# HelpfulHallway.net
KiCad netlist of a schematic drawn in EAGLE
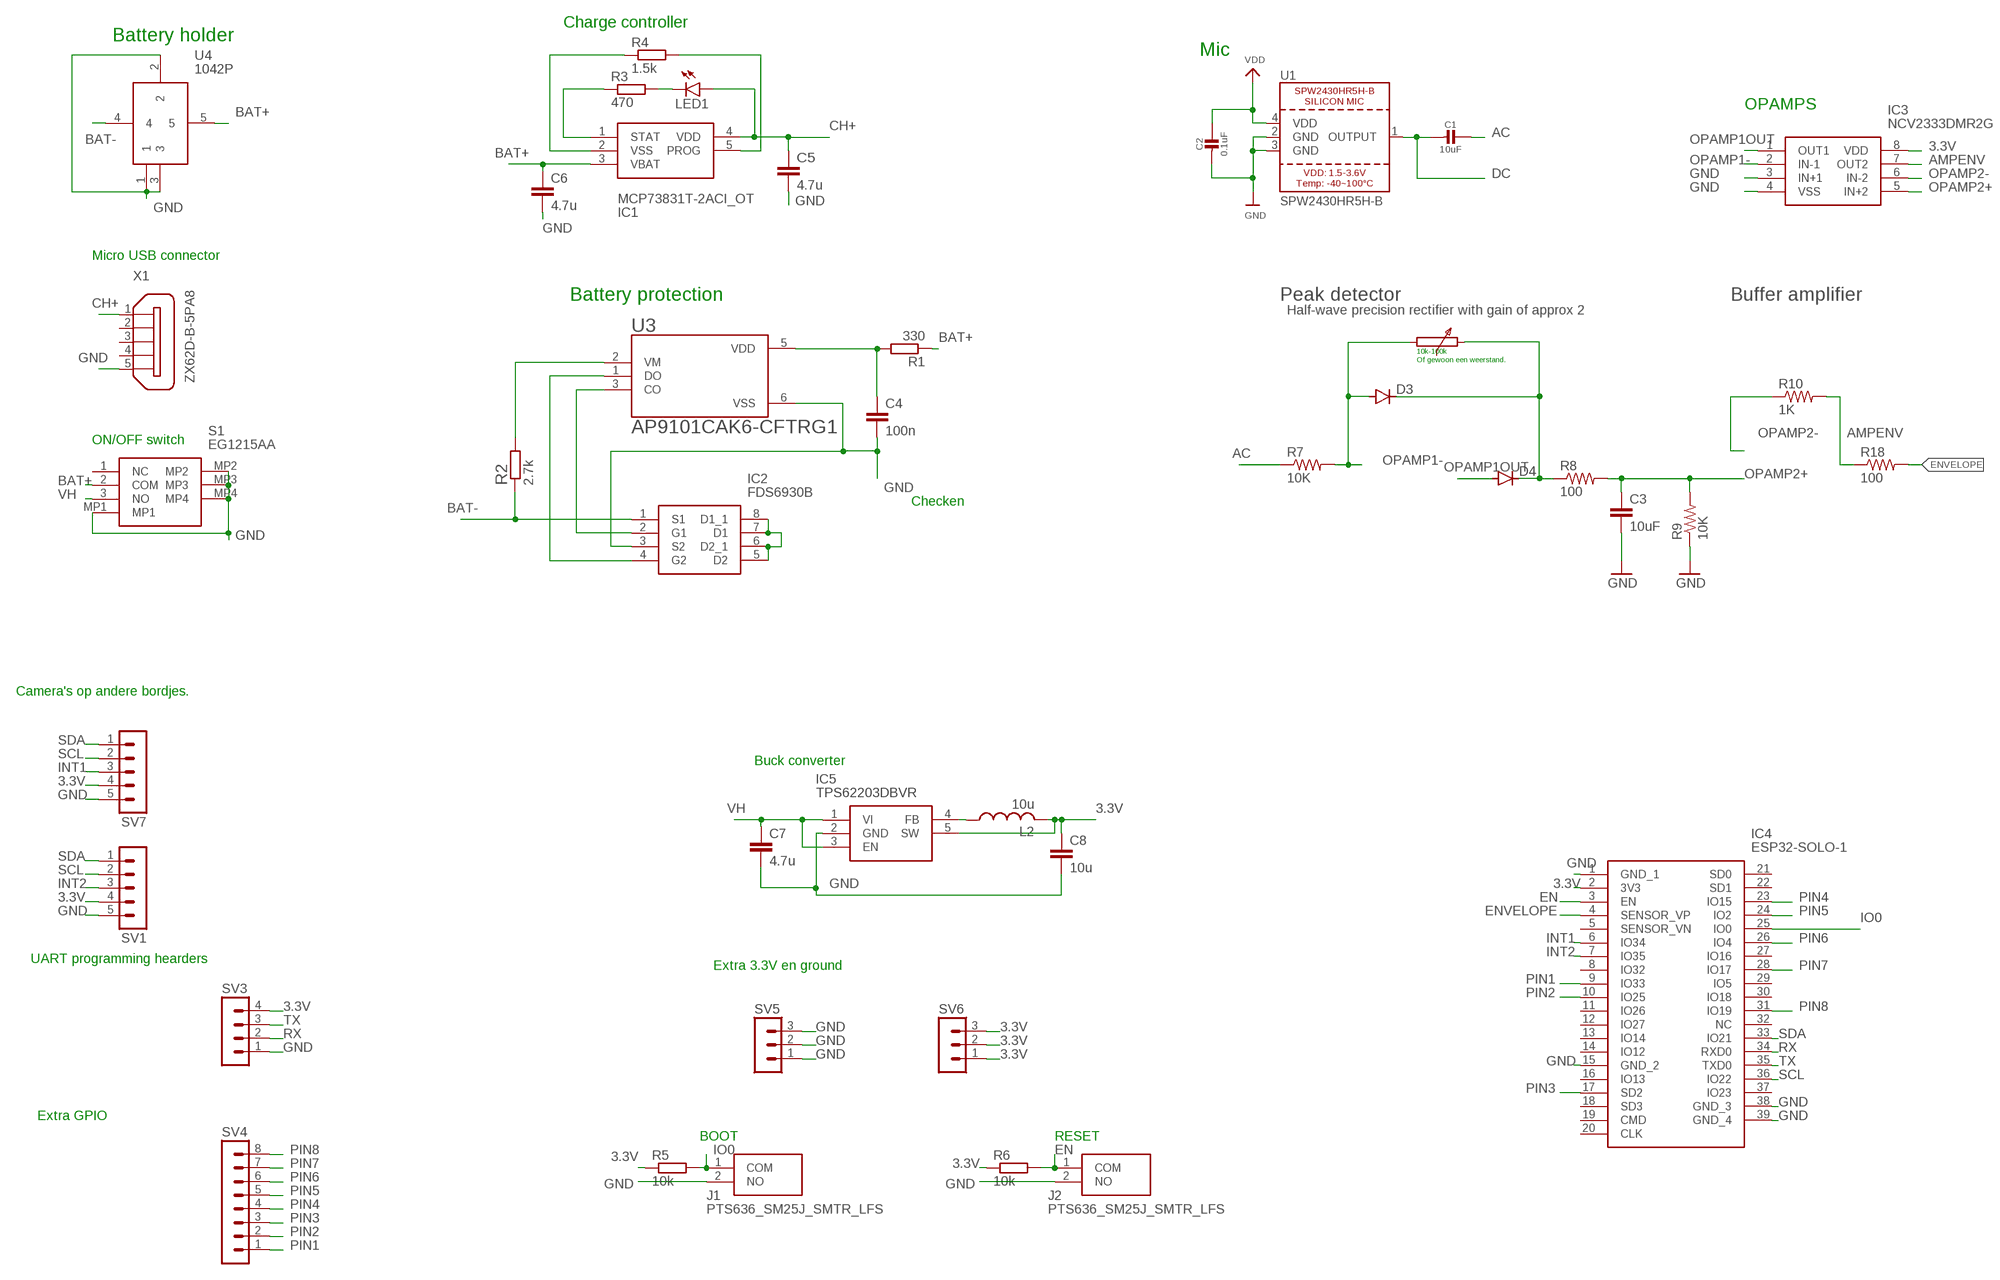
[diagram p0: schematic, sheet 1]

(export (version "E")
  (design (tool "Eeschema 10.0.6"))
  (components
    (comp (ref "C1")
      (value "10uF")
      (footprint "eagle-import:0805-NO")
      (libsource (lib "eagle-import") (part "CAP_CERAMIC0805-NOOUTLINE"))
    )
    (comp (ref "C2")
      (value "0.1uF")
      (footprint "eagle-import:0805-NO")
      (libsource (lib "eagle-import") (part "CAP_CERAMIC0805-NOOUTLINE"))
    )
    (comp (ref "C3")
      (value "10uF")
      (footprint "eagle-import:1206")
      (libsource (lib "eagle-import") (part "10UF-6.3V-20%(1206)"))
    )
    (comp (ref "C4")
      (value "100n")
      (footprint "eagle-import:C1206")
      (libsource (lib "eagle-import") (part "C-EUC1206"))
    )
    (comp (ref "C5")
      (value "4.7u")
      (footprint "eagle-import:C1206")
      (libsource (lib "eagle-import") (part "C-EUC1206"))
    )
    (comp (ref "C6")
      (value "4.7u")
      (footprint "eagle-import:C1206")
      (libsource (lib "eagle-import") (part "C-EUC1206"))
    )
    (comp (ref "C7")
      (value "4.7u")
      (footprint "eagle-import:C1206")
      (libsource (lib "eagle-import") (part "C-EUC1206"))
    )
    (comp (ref "C8")
      (value "10u")
      (footprint "eagle-import:C1206")
      (libsource (lib "eagle-import") (part "C-EUC1206"))
    )
    (comp (ref "D3")
      (value "DIODE-SOD123")
      (footprint "eagle-import:SOD123")
      (libsource (lib "eagle-import") (part "DIODE-SOD123"))
    )
    (comp (ref "D4")
      (value "DIODE-SOD123")
      (footprint "eagle-import:SOD123")
      (libsource (lib "eagle-import") (part "DIODE-SOD123"))
    )
    (comp (ref "IC1")
      (value "MCP73831T-2ACI_OT")
      (footprint "eagle-import:SOT95P270X145-5N")
      (fields
        (field (name "MANUFACTURER_PART_NUMBER") "MCP73831T-2ACI/OT")
        (field (name "MOUSER_PART_NUMBER") "579-MCP73831T-2ACIOT")
      )
      (libsource (lib "eagle-import") (part "MCP73831T-2ACI_OT"))
    )
    (comp (ref "IC2")
      (value "FDS6930B")
      (footprint "eagle-import:SOIC127P600X175-8N")
      (fields (field (name "MOUSER_PART_NUMBER") "512-FDS6930B"))
      (libsource (lib "eagle-import") (part "FDS6930B"))
    )
    (comp (ref "IC3")
      (value "NCV2333DMR2G")
      (footprint "eagle-import:SOP65P490X110-8N")
      (fields (field (name "MOUSER_PART_NUMBER") "863-NCV2333DMR2G"))
      (libsource (lib "eagle-import") (part "NCV2333DMR2G"))
    )
    (comp (ref "IC4")
      (value "ESP32-SOLO-1")
      (footprint "eagle-import:ESP32SOLO1")
      (fields (field (name "MOUSER_PART_NUMBER") "356-ESP32-SOLO-1"))
      (libsource (lib "eagle-import") (part "ESP32-SOLO-1"))
    )
    (comp (ref "IC5")
      (value "TPS62203DBVR")
      (footprint "eagle-import:SOT95P280X145-5N")
      (fields (field (name "MOUSER_PART_NUMBER") "595-TPS62203DBVR"))
      (libsource (lib "eagle-import") (part "TPS62203DBVR"))
    )
    (comp (ref "J1")
      (value "PTS636_SM25J_SMTR_LFS")
      (footprint "eagle-import:PTS636SM25JSMTRLFS")
      (fields
        (field (name "MANUFACTURER_PART_NUMBER") "PTS636 SM25J SMTR LFS")
        (field (name "MOUSER_PART_NUMBER") "611-PTS636SM25JSMTRL")
      )
      (libsource (lib "eagle-import") (part "PTS636_SM25J_SMTR_LFS"))
    )
    (comp (ref "J2")
      (value "PTS636_SM25J_SMTR_LFS")
      (footprint "eagle-import:PTS636SM25JSMTRLFS")
      (fields
        (field (name "MANUFACTURER_PART_NUMBER") "PTS636 SM25J SMTR LFS")
        (field (name "MOUSER_PART_NUMBER") "611-PTS636SM25JSMTRL")
      )
      (libsource (lib "eagle-import") (part "PTS636_SM25J_SMTR_LFS"))
    )
    (comp (ref "L2")
      (value "10u")
      (footprint "eagle-import:L4532P")
      (libsource (lib "eagle-import") (part "L-USL4532P"))
    )
    (comp (ref "LED1")
      (value "LEDSMT1206")
      (footprint "eagle-import:1206")
      (libsource (lib "eagle-import") (part "LEDSMT1206"))
    )
    (comp (ref "R1")
      (value "330")
      (footprint "eagle-import:R1206")
      (libsource (lib "eagle-import") (part "resistor_348_R-EU_R1206"))
    )
    (comp (ref "R2")
      (value "2.7k")
      (footprint "eagle-import:R1206")
      (libsource (lib "eagle-import") (part "resistor_348_R-EU_R1206"))
    )
    (comp (ref "R3")
      (value "470")
      (footprint "eagle-import:R1206")
      (libsource (lib "eagle-import") (part "resistor_348_R-EU_R1206"))
    )
    (comp (ref "R4")
      (value "1.5k")
      (footprint "eagle-import:R1206")
      (libsource (lib "eagle-import") (part "R-EU_R1206"))
    )
    (comp (ref "R5")
      (value "10k")
      (footprint "eagle-import:M1206")
      (libsource (lib "eagle-import") (part "R-EU_M1206"))
    )
    (comp (ref "R6")
      (value "10k")
      (footprint "eagle-import:M1206")
      (libsource (lib "eagle-import") (part "R-EU_M1206"))
    )
    (comp (ref "R7")
      (value "10K")
      (footprint "eagle-import:0603-RES")
      (libsource (lib "eagle-import") (part "10KOHM1/10W1%(0603)0603"))
    )
    (comp (ref "R8")
      (value "100")
      (footprint "eagle-import:0603-RES")
      (libsource (lib "eagle-import") (part "100OHM1/10W1%(0603)"))
    )
    (comp (ref "R9")
      (value "10K")
      (footprint "eagle-import:0603-RES")
      (libsource (lib "eagle-import") (part "10KOHM1/10W1%(0603)0603"))
    )
    (comp (ref "R10")
      (value "1K")
      (footprint "eagle-import:0603-RES")
      (libsource (lib "eagle-import") (part "1KOHM1/10W1%(0603)"))
    )
    (comp (ref "R18")
      (value "100")
      (footprint "eagle-import:0603-RES")
      (libsource (lib "eagle-import") (part "100OHM1/10W1%(0603)"))
    )
    (comp (ref "S1")
      (value "EG1215AA")
      (footprint "eagle-import:EG1215AA")
      (fields (field (name "MOUSER_PART_NUMBER") "612-EG1215AA"))
      (libsource (lib "eagle-import") (part "EG1215AA"))
    )
    (comp (ref "SV1")
      (value "MA05-1")
      (footprint "eagle-import:MA05-1")
      (libsource (lib "eagle-import") (part "MA05-1"))
    )
    (comp (ref "SV3")
      (value "MA04-1")
      (footprint "eagle-import:MA04-1")
      (libsource (lib "eagle-import") (part "MA04-1"))
    )
    (comp (ref "SV4")
      (value "MA08-1")
      (footprint "eagle-import:MA08-1")
      (libsource (lib "eagle-import") (part "MA08-1"))
    )
    (comp (ref "SV5")
      (value "MA03-1")
      (footprint "eagle-import:MA03-1")
      (libsource (lib "eagle-import") (part "MA03-1"))
    )
    (comp (ref "SV6")
      (value "MA03-1")
      (footprint "eagle-import:MA03-1")
      (libsource (lib "eagle-import") (part "MA03-1"))
    )
    (comp (ref "SV7")
      (value "MA05-1")
      (footprint "eagle-import:MA05-1")
      (libsource (lib "eagle-import") (part "MA05-1"))
    )
    (comp (ref "U1")
      (value "SPW2430HR5H-B")
      (footprint "eagle-import:SPW2430HR5H-B")
      (libsource (lib "eagle-import") (part "SPW2430HR5H-B"))
    )
    (comp (ref "U3")
      (value "AP9101CAK6-CFTRG1")
      (footprint "eagle-import:SOT95P280X140-6N")
      (fields (field (name "MF") "Diodes Inc."))
      (libsource (lib "eagle-import") (part "AP9101CAK6-CFTRG1"))
    )
    (comp (ref "U4")
      (value "1042P")
      (footprint "eagle-import:1042P")
      (fields (field (name "MOUSER_PART_NUMBER") "534-1042P"))
      (libsource (lib "eagle-import") (part "1042P"))
    )
    (comp (ref "X1")
      (value "ZX62D-B-5PA8")
      (footprint "eagle-import:ZX62D-B-5PA8")
      (fields (field (name "MF") "Hirose"))
      (libsource (lib "eagle-import") (part "ZX62D-B-5PA8"))
    )
  )
  (nets
    (net (code "1") (name "/3.3V") (class "Default")
      (node (ref "C8") (pin "1") (pinfunction "1_1") (pintype "passive"))
      (node (ref "IC3") (pin "8") (pinfunction "VDD_8") (pintype "bidirectional"))
      (node (ref "IC4") (pin "2") (pinfunction "3V3_2") (pintype "bidirectional"))
      (node (ref "IC5") (pin "5") (pinfunction "SW_5") (pintype "bidirectional"))
      (node (ref "L2") (pin "2") (pinfunction "2_2") (pintype "passive"))
      (node (ref "R5") (pin "1") (pinfunction "1_1") (pintype "passive"))
      (node (ref "R6") (pin "1") (pinfunction "1_1") (pintype "passive"))
      (node (ref "SV1") (pin "4") (pinfunction "4_4") (pintype "passive"))
      (node (ref "SV3") (pin "4") (pinfunction "4_4") (pintype "passive"))
      (node (ref "SV6") (pin "1") (pinfunction "1_1") (pintype "passive"))
      (node (ref "SV6") (pin "2") (pinfunction "2_2") (pintype "passive"))
      (node (ref "SV6") (pin "3") (pinfunction "3_3") (pintype "passive"))
      (node (ref "SV7") (pin "4") (pinfunction "4_4") (pintype "passive"))
    )
    (net (code "2") (name "/AC") (class "Default")
      (node (ref "C1") (pin "1") (pinfunction "1_1") (pintype "passive"))
      (node (ref "R7") (pin "1") (pinfunction "1_1") (pintype "passive"))
    )
    (net (code "3") (name "/AMPENV") (class "Default")
      (node (ref "IC3") (pin "7") (pinfunction "OUT2_7") (pintype "bidirectional"))
      (node (ref "R10") (pin "2") (pinfunction "2_2") (pintype "passive"))
      (node (ref "R18") (pin "1") (pinfunction "1_1") (pintype "passive"))
    )
    (net (code "4") (name "/BAT+") (class "Default")
      (node (ref "C6") (pin "1") (pinfunction "1_1") (pintype "passive"))
      (node (ref "IC1") (pin "3") (pinfunction "VBAT_3") (pintype "bidirectional"))
      (node (ref "R1") (pin "1") (pinfunction "1_1") (pintype "passive"))
      (node (ref "S1") (pin "2") (pinfunction "COM_2") (pintype "bidirectional"))
      (node (ref "U4") (pin "5") (pinfunction "5_5") (pintype "bidirectional"))
    )
    (net (code "5") (name "/BAT-") (class "Default")
      (node (ref "IC2") (pin "1") (pinfunction "S1_1") (pintype "bidirectional"))
      (node (ref "R2") (pin "1") (pinfunction "1_1") (pintype "passive"))
      (node (ref "U4") (pin "4") (pinfunction "4_4") (pintype "bidirectional"))
    )
    (net (code "6") (name "/CH+") (class "Default")
      (node (ref "C5") (pin "1") (pinfunction "1_1") (pintype "passive"))
      (node (ref "IC1") (pin "4") (pinfunction "VDD_4") (pintype "power_in"))
      (node (ref "LED1") (pin "A") (pinfunction "A_A") (pintype "passive"))
      (node (ref "X1") (pin "1") (pinfunction "1_1") (pintype "passive"))
    )
    (net (code "7") (name "/DC") (class "Default")
      (node (ref "C1") (pin "2") (pinfunction "2_2") (pintype "passive"))
      (node (ref "U1") (pin "1") (pinfunction "OUTPUT_1") (pintype "output"))
    )
    (net (code "8") (name "/EN") (class "Default")
      (node (ref "IC4") (pin "3") (pinfunction "EN_3") (pintype "bidirectional"))
      (node (ref "J2") (pin "1") (pinfunction "COM_1") (pintype "bidirectional"))
      (node (ref "R6") (pin "2") (pinfunction "2_2") (pintype "passive"))
    )
    (net (code "9") (name "/INT1") (class "Default")
      (node (ref "IC4") (pin "6") (pinfunction "IO34_6") (pintype "bidirectional"))
      (node (ref "SV7") (pin "3") (pinfunction "3_3") (pintype "passive"))
    )
    (net (code "10") (name "/INT2") (class "Default")
      (node (ref "IC4") (pin "7") (pinfunction "IO35_7") (pintype "bidirectional"))
      (node (ref "SV1") (pin "3") (pinfunction "3_3") (pintype "passive"))
    )
    (net (code "11") (name "/IO0") (class "Default")
      (node (ref "IC4") (pin "25") (pinfunction "IO0_25") (pintype "bidirectional"))
      (node (ref "J1") (pin "1") (pinfunction "COM_1") (pintype "bidirectional"))
      (node (ref "R5") (pin "2") (pinfunction "2_2") (pintype "passive"))
    )
    (net (code "12") (name "/OPAMP1-") (class "Default")
      (node (ref "D3") (pin "A") (pinfunction "A_A") (pintype "passive"))
      (node (ref "IC3") (pin "2") (pinfunction "IN-1_2") (pintype "bidirectional"))
      (node (ref "R7") (pin "2") (pinfunction "2_2") (pintype "passive"))
    )
    (net (code "13") (name "/OPAMP1OUT") (class "Default")
      (node (ref "D4") (pin "A") (pinfunction "A_A") (pintype "passive"))
      (node (ref "IC3") (pin "1") (pinfunction "OUT1_1") (pintype "bidirectional"))
    )
    (net (code "14") (name "/OPAMP2+") (class "Default")
      (node (ref "C3") (pin "1") (pinfunction "1_1") (pintype "passive"))
      (node (ref "IC3") (pin "5") (pinfunction "IN+2_5") (pintype "bidirectional"))
      (node (ref "R8") (pin "2") (pinfunction "2_2") (pintype "passive"))
      (node (ref "R9") (pin "2") (pinfunction "2_2") (pintype "passive"))
    )
    (net (code "15") (name "/OPAMP2-") (class "Default")
      (node (ref "IC3") (pin "6") (pinfunction "IN-2_6") (pintype "bidirectional"))
      (node (ref "R10") (pin "1") (pinfunction "1_1") (pintype "passive"))
    )
    (net (code "16") (name "/PIN1") (class "Default")
      (node (ref "IC4") (pin "9") (pinfunction "IO33_9") (pintype "bidirectional"))
      (node (ref "SV4") (pin "1") (pinfunction "1_1") (pintype "passive"))
    )
    (net (code "17") (name "/PIN2") (class "Default")
      (node (ref "IC4") (pin "10") (pinfunction "IO25_10") (pintype "bidirectional"))
      (node (ref "SV4") (pin "2") (pinfunction "2_2") (pintype "passive"))
    )
    (net (code "18") (name "/PIN3") (class "Default")
      (node (ref "IC4") (pin "17") (pinfunction "SD2_17") (pintype "bidirectional"))
      (node (ref "SV4") (pin "3") (pinfunction "3_3") (pintype "passive"))
    )
    (net (code "19") (name "/PIN4") (class "Default")
      (node (ref "IC4") (pin "23") (pinfunction "IO15_23") (pintype "bidirectional"))
      (node (ref "SV4") (pin "4") (pinfunction "4_4") (pintype "passive"))
    )
    (net (code "20") (name "/PIN5") (class "Default")
      (node (ref "IC4") (pin "24") (pinfunction "IO2_24") (pintype "bidirectional"))
      (node (ref "SV4") (pin "5") (pinfunction "5_5") (pintype "passive"))
    )
    (net (code "21") (name "/PIN6") (class "Default")
      (node (ref "IC4") (pin "26") (pinfunction "IO4_26") (pintype "bidirectional"))
      (node (ref "SV4") (pin "6") (pinfunction "6_6") (pintype "passive"))
    )
    (net (code "22") (name "/PIN7") (class "Default")
      (node (ref "IC4") (pin "28") (pinfunction "IO17_28") (pintype "bidirectional"))
      (node (ref "SV4") (pin "7") (pinfunction "7_7") (pintype "passive"))
    )
    (net (code "23") (name "/PIN8") (class "Default")
      (node (ref "IC4") (pin "31") (pinfunction "IO19_31") (pintype "bidirectional"))
      (node (ref "SV4") (pin "8") (pinfunction "8_8") (pintype "passive"))
    )
    (net (code "24") (name "/RX") (class "Default")
      (node (ref "IC4") (pin "34") (pinfunction "RXD0_34") (pintype "bidirectional"))
      (node (ref "SV3") (pin "2") (pinfunction "2_2") (pintype "passive"))
    )
    (net (code "25") (name "/SCL") (class "Default")
      (node (ref "IC4") (pin "36") (pinfunction "IO22_36") (pintype "bidirectional"))
      (node (ref "SV1") (pin "2") (pinfunction "2_2") (pintype "passive"))
      (node (ref "SV7") (pin "2") (pinfunction "2_2") (pintype "passive"))
    )
    (net (code "26") (name "/SDA") (class "Default")
      (node (ref "IC4") (pin "33") (pinfunction "IO21_33") (pintype "bidirectional"))
      (node (ref "SV1") (pin "1") (pinfunction "1_1") (pintype "passive"))
      (node (ref "SV7") (pin "1") (pinfunction "1_1") (pintype "passive"))
    )
    (net (code "27") (name "/TX") (class "Default")
      (node (ref "IC4") (pin "35") (pinfunction "TXD0_35") (pintype "bidirectional"))
      (node (ref "SV3") (pin "3") (pinfunction "3_3") (pintype "passive"))
    )
    (net (code "28") (name "/VH") (class "Default")
      (node (ref "C7") (pin "1") (pinfunction "1_1") (pintype "passive"))
      (node (ref "IC5") (pin "1") (pinfunction "VI_1") (pintype "bidirectional"))
      (node (ref "IC5") (pin "3") (pinfunction "EN_3") (pintype "bidirectional"))
      (node (ref "S1") (pin "3") (pinfunction "NO_3") (pintype "bidirectional"))
    )
    (net (code "29") (name "ENVELOPE") (class "Default")
      (node (ref "IC4") (pin "4") (pinfunction "SENSOR_VP_4") (pintype "bidirectional"))
      (node (ref "R18") (pin "2") (pinfunction "2_2") (pintype "passive"))
    )
    (net (code "30") (name "GND") (class "Default")
      (node (ref "C2") (pin "2") (pinfunction "2_2") (pintype "passive"))
      (node (ref "C3") (pin "2") (pinfunction "2_2") (pintype "passive"))
      (node (ref "C4") (pin "2") (pinfunction "2_2") (pintype "passive"))
      (node (ref "C5") (pin "2") (pinfunction "2_2") (pintype "passive"))
      (node (ref "C6") (pin "2") (pinfunction "2_2") (pintype "passive"))
      (node (ref "C7") (pin "2") (pinfunction "2_2") (pintype "passive"))
      (node (ref "C8") (pin "2") (pinfunction "2_2") (pintype "passive"))
      (node (ref "IC2") (pin "3") (pinfunction "S2_3") (pintype "bidirectional"))
      (node (ref "IC3") (pin "3") (pinfunction "IN+1_3") (pintype "bidirectional"))
      (node (ref "IC3") (pin "4") (pinfunction "VSS_4") (pintype "bidirectional"))
      (node (ref "IC4") (pin "1") (pinfunction "GND_1_1") (pintype "bidirectional"))
      (node (ref "IC4") (pin "15") (pinfunction "GND_2_15") (pintype "bidirectional"))
      (node (ref "IC4") (pin "38") (pinfunction "GND_3_38") (pintype "bidirectional"))
      (node (ref "IC4") (pin "39") (pinfunction "GND_4_39") (pintype "bidirectional"))
      (node (ref "IC5") (pin "2") (pinfunction "GND_2") (pintype "bidirectional"))
      (node (ref "J1") (pin "2") (pinfunction "NO_2") (pintype "bidirectional"))
      (node (ref "J2") (pin "2") (pinfunction "NO_2") (pintype "bidirectional"))
      (node (ref "R9") (pin "1") (pinfunction "1_1") (pintype "passive"))
      (node (ref "S1") (pin "MP1") (pinfunction "MP1_MP1") (pintype "bidirectional"))
      (node (ref "S1") (pin "MP2") (pinfunction "MP2_MP2") (pintype "bidirectional"))
      (node (ref "S1") (pin "MP3") (pinfunction "MP3_MP3") (pintype "bidirectional"))
      (node (ref "S1") (pin "MP4") (pinfunction "MP4_MP4") (pintype "bidirectional"))
      (node (ref "SV1") (pin "5") (pinfunction "5_5") (pintype "passive"))
      (node (ref "SV3") (pin "1") (pinfunction "1_1") (pintype "passive"))
      (node (ref "SV5") (pin "1") (pinfunction "1_1") (pintype "passive"))
      (node (ref "SV5") (pin "2") (pinfunction "2_2") (pintype "passive"))
      (node (ref "SV5") (pin "3") (pinfunction "3_3") (pintype "passive"))
      (node (ref "SV7") (pin "5") (pinfunction "5_5") (pintype "passive"))
      (node (ref "U1") (pin "2") (pinfunction "GND_2") (pintype "power_in"))
      (node (ref "U1") (pin "3") (pinfunction "GND_3") (pintype "power_in"))
      (node (ref "U3") (pin "6") (pinfunction "VSS_6") (pintype "power_in"))
      (node (ref "U4") (pin "1") (pinfunction "1_1") (pintype "bidirectional"))
      (node (ref "U4") (pin "2") (pinfunction "2_2") (pintype "bidirectional"))
      (node (ref "U4") (pin "3") (pinfunction "3_3") (pintype "bidirectional"))
      (node (ref "X1") (pin "5") (pinfunction "5_5") (pintype "passive"))
    )
    (net (code "31") (name "Net-(D3-PadC)") (class "Default")
      (node (ref "D3") (pin "C") (pinfunction "C_C") (pintype "passive"))
      (node (ref "D4") (pin "C") (pinfunction "C_C") (pintype "passive"))
      (node (ref "R8") (pin "1") (pinfunction "1_1") (pintype "passive"))
    )
    (net (code "32") (name "Net-(IC1-PROG)") (class "Default")
      (node (ref "IC1") (pin "5") (pinfunction "PROG_5") (pintype "bidirectional"))
      (node (ref "R4") (pin "2") (pinfunction "2_2") (pintype "passive"))
    )
    (net (code "33") (name "Net-(IC1-STAT)") (class "Default")
      (node (ref "IC1") (pin "1") (pinfunction "STAT_1") (pintype "bidirectional"))
      (node (ref "R3") (pin "1") (pinfunction "1_1") (pintype "passive"))
    )
    (net (code "34") (name "Net-(IC1-VSS)") (class "Default")
      (node (ref "IC1") (pin "2") (pinfunction "VSS_2") (pintype "power_in"))
      (node (ref "R4") (pin "1") (pinfunction "1_1") (pintype "passive"))
    )
    (net (code "35") (name "Net-(IC2-D1)") (class "Default")
      (node (ref "IC2") (pin "5") (pinfunction "D2_5") (pintype "bidirectional"))
      (node (ref "IC2") (pin "6") (pinfunction "D2_1_6") (pintype "bidirectional"))
      (node (ref "IC2") (pin "7") (pinfunction "D1_7") (pintype "bidirectional"))
      (node (ref "IC2") (pin "8") (pinfunction "D1_1_8") (pintype "bidirectional"))
    )
    (net (code "36") (name "Net-(IC2-G1)") (class "Default")
      (node (ref "IC2") (pin "2") (pinfunction "G1_2") (pintype "bidirectional"))
      (node (ref "U3") (pin "3") (pinfunction "CO_3") (pintype "bidirectional"))
    )
    (net (code "37") (name "Net-(IC2-G2)") (class "Default")
      (node (ref "IC2") (pin "4") (pinfunction "G2_4") (pintype "bidirectional"))
      (node (ref "U3") (pin "1") (pinfunction "DO_1") (pintype "bidirectional"))
    )
    (net (code "38") (name "Net-(IC5-FB)") (class "Default")
      (node (ref "IC5") (pin "4") (pinfunction "FB_4") (pintype "bidirectional"))
      (node (ref "L2") (pin "1") (pinfunction "1_1") (pintype "passive"))
    )
    (net (code "39") (name "Net-(LED1-PadC)") (class "Default")
      (node (ref "LED1") (pin "C") (pinfunction "C_C") (pintype "passive"))
      (node (ref "R3") (pin "2") (pinfunction "2_2") (pintype "passive"))
    )
    (net (code "40") (name "Net-(U3-VDD)") (class "Default")
      (node (ref "C4") (pin "1") (pinfunction "1_1") (pintype "passive"))
      (node (ref "R1") (pin "2") (pinfunction "2_2") (pintype "passive"))
      (node (ref "U3") (pin "5") (pinfunction "VDD_5") (pintype "power_in"))
    )
    (net (code "41") (name "Net-(U3-VM)") (class "Default")
      (node (ref "R2") (pin "2") (pinfunction "2_2") (pintype "passive"))
      (node (ref "U3") (pin "2") (pinfunction "VM_2") (pintype "input"))
    )
    (net (code "42") (name "VDD") (class "Default")
      (node (ref "C2") (pin "1") (pinfunction "1_1") (pintype "passive"))
      (node (ref "U1") (pin "4") (pinfunction "VDD_4") (pintype "power_in"))
    )
    (net (code "43") (name "unconnected-(IC4-CLK-Pad20)") (class "Default")
      (node (ref "IC4") (pin "20") (pinfunction "CLK_20") (pintype "bidirectional"))
    )
    (net (code "44") (name "unconnected-(IC4-CMD-Pad19)") (class "Default")
      (node (ref "IC4") (pin "19") (pinfunction "CMD_19") (pintype "bidirectional"))
    )
    (net (code "45") (name "unconnected-(IC4-IO5-Pad29)") (class "Default")
      (node (ref "IC4") (pin "29") (pinfunction "IO5_29") (pintype "bidirectional"))
    )
    (net (code "46") (name "unconnected-(IC4-IO12-Pad14)") (class "Default")
      (node (ref "IC4") (pin "14") (pinfunction "IO12_14") (pintype "bidirectional"))
    )
    (net (code "47") (name "unconnected-(IC4-IO13-Pad16)") (class "Default")
      (node (ref "IC4") (pin "16") (pinfunction "IO13_16") (pintype "bidirectional"))
    )
    (net (code "48") (name "unconnected-(IC4-IO14-Pad13)") (class "Default")
      (node (ref "IC4") (pin "13") (pinfunction "IO14_13") (pintype "bidirectional"))
    )
    (net (code "49") (name "unconnected-(IC4-IO16-Pad27)") (class "Default")
      (node (ref "IC4") (pin "27") (pinfunction "IO16_27") (pintype "bidirectional"))
    )
    (net (code "50") (name "unconnected-(IC4-IO18-Pad30)") (class "Default")
      (node (ref "IC4") (pin "30") (pinfunction "IO18_30") (pintype "bidirectional"))
    )
    (net (code "51") (name "unconnected-(IC4-IO23-Pad37)") (class "Default")
      (node (ref "IC4") (pin "37") (pinfunction "IO23_37") (pintype "bidirectional"))
    )
    (net (code "52") (name "unconnected-(IC4-IO26-Pad11)") (class "Default")
      (node (ref "IC4") (pin "11") (pinfunction "IO26_11") (pintype "bidirectional"))
    )
    (net (code "53") (name "unconnected-(IC4-IO27-Pad12)") (class "Default")
      (node (ref "IC4") (pin "12") (pinfunction "IO27_12") (pintype "bidirectional"))
    )
    (net (code "54") (name "unconnected-(IC4-IO32-Pad8)") (class "Default")
      (node (ref "IC4") (pin "8") (pinfunction "IO32_8") (pintype "bidirectional"))
    )
    (net (code "55") (name "unconnected-(IC4-NC-Pad32)") (class "Default")
      (node (ref "IC4") (pin "32") (pinfunction "NC_32") (pintype "no_connect"))
    )
    (net (code "56") (name "unconnected-(IC4-SD0-Pad21)") (class "Default")
      (node (ref "IC4") (pin "21") (pinfunction "SD0_21") (pintype "bidirectional"))
    )
    (net (code "57") (name "unconnected-(IC4-SD1-Pad22)") (class "Default")
      (node (ref "IC4") (pin "22") (pinfunction "SD1_22") (pintype "bidirectional"))
    )
    (net (code "58") (name "unconnected-(IC4-SD3-Pad18)") (class "Default")
      (node (ref "IC4") (pin "18") (pinfunction "SD3_18") (pintype "bidirectional"))
    )
    (net (code "59") (name "unconnected-(IC4-SENSOR_VN-Pad5)") (class "Default")
      (node (ref "IC4") (pin "5") (pinfunction "SENSOR_VN_5") (pintype "bidirectional"))
    )
    (net (code "60") (name "unconnected-(S1-NC-Pad1)") (class "Default")
      (node (ref "S1") (pin "1") (pinfunction "NC_1") (pintype "no_connect"))
    )
    (net (code "61") (name "unconnected-(X1-Pad2)") (class "Default")
      (node (ref "X1") (pin "2") (pinfunction "2_2") (pintype "passive"))
    )
    (net (code "62") (name "unconnected-(X1-Pad3)") (class "Default")
      (node (ref "X1") (pin "3") (pinfunction "3_3") (pintype "passive"))
    )
    (net (code "63") (name "unconnected-(X1-Pad4)") (class "Default")
      (node (ref "X1") (pin "4") (pinfunction "4_4") (pintype "passive"))
    )
  )
)
